# 08_STORE.net
KiCad netlist of a schematic drawn in EAGLE
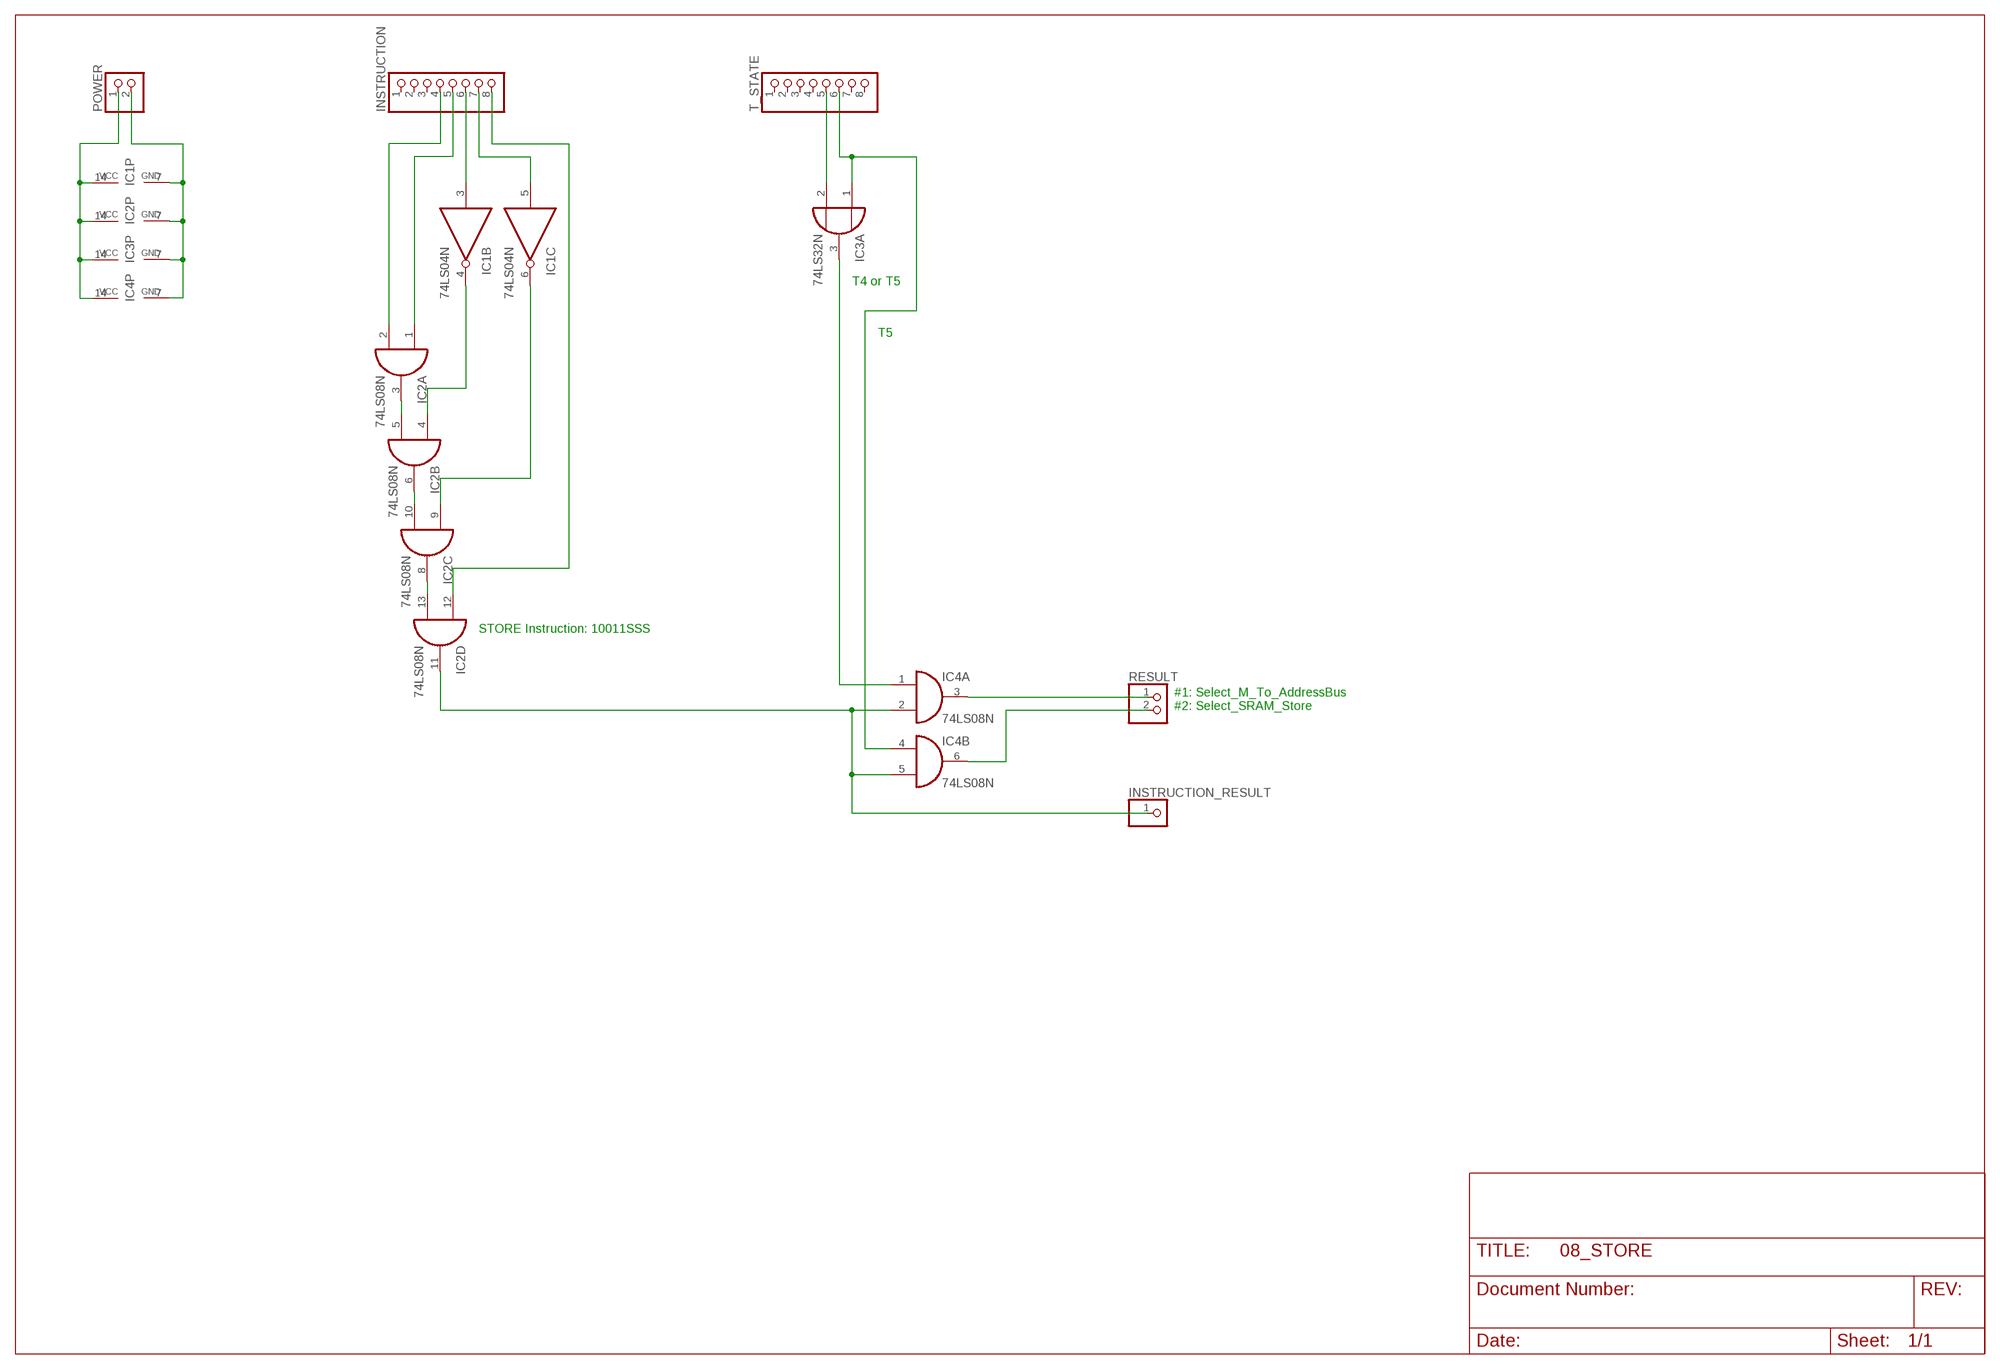
[diagram p0: schematic, sheet 1]

(export (version "E")
  (design (tool "Eeschema 10.0.6"))
  (components
    (comp (ref "IC1")
      (value "74LS04N")
      (footprint "eagle-import:DIL14")
      (libsource (lib "eagle-import") (part "7404NLS"))
    )
    (comp (ref "IC2")
      (value "74LS08N")
      (footprint "eagle-import:DIL14")
      (libsource (lib "eagle-import") (part "7408NLS"))
    )
    (comp (ref "IC3")
      (value "74LS32N")
      (footprint "eagle-import:DIL14")
      (libsource (lib "eagle-import") (part "7432NLS"))
    )
    (comp (ref "IC4")
      (value "74LS08N")
      (footprint "eagle-import:DIL14")
      (libsource (lib "eagle-import") (part "7408NLS"))
    )
    (comp (ref "INSTRUCTION")
      (value "PINHD-1X8")
      (footprint "eagle-import:1X08")
      (libsource (lib "eagle-import") (part "PINHD-1X8"))
    )
    (comp (ref "INSTRUCTION_RESULT")
      (value "PINHD-1X1")
      (footprint "eagle-import:1X01")
      (libsource (lib "eagle-import") (part "PINHD-1X1"))
    )
    (comp (ref "POWER")
      (value "PINHD-1X2")
      (footprint "eagle-import:1X02")
      (libsource (lib "eagle-import") (part "PINHD-1X2"))
    )
    (comp (ref "RESULT")
      (value "PINHD-1X2")
      (footprint "eagle-import:1X02")
      (libsource (lib "eagle-import") (part "PINHD-1X2"))
    )
    (comp (ref "T_STATE")
      (value "PINHD-1X8")
      (footprint "eagle-import:1X08")
      (libsource (lib "eagle-import") (part "PINHD-1X8"))
    )
  )
  (nets
    (net (code "1") (name "Net-(IC1B-I)") (class "Default")
      (node (ref "IC1") (pin "3") (pinfunction "I_3") (pintype "input"))
      (node (ref "INSTRUCTION") (pin "6") (pinfunction "6_6") (pintype "passive"))
    )
    (net (code "2") (name "Net-(IC1B-O)") (class "Default")
      (node (ref "IC1") (pin "4") (pinfunction "O_4") (pintype "output"))
      (node (ref "IC2") (pin "4") (pinfunction "I0_4") (pintype "input"))
    )
    (net (code "3") (name "Net-(IC1C-I)") (class "Default")
      (node (ref "IC1") (pin "5") (pinfunction "I_5") (pintype "input"))
      (node (ref "INSTRUCTION") (pin "7") (pinfunction "7_7") (pintype "passive"))
    )
    (net (code "4") (name "Net-(IC1C-O)") (class "Default")
      (node (ref "IC1") (pin "6") (pinfunction "O_6") (pintype "output"))
      (node (ref "IC2") (pin "9") (pinfunction "I0_9") (pintype "input"))
    )
    (net (code "5") (name "Net-(IC1G-GND)") (class "Default")
      (node (ref "IC1") (pin "7") (pinfunction "GND_7") (pintype "power_in"))
      (node (ref "IC2") (pin "7") (pinfunction "GND_7") (pintype "power_in"))
      (node (ref "IC3") (pin "7") (pinfunction "GND_7") (pintype "power_in"))
      (node (ref "IC4") (pin "7") (pinfunction "GND_7") (pintype "power_in"))
      (node (ref "POWER") (pin "2") (pinfunction "2_2") (pintype "passive"))
    )
    (net (code "6") (name "Net-(IC1G-VCC)") (class "Default")
      (node (ref "IC1") (pin "14") (pinfunction "VCC_14") (pintype "power_in"))
      (node (ref "IC2") (pin "14") (pinfunction "VCC_14") (pintype "power_in"))
      (node (ref "IC3") (pin "14") (pinfunction "VCC_14") (pintype "power_in"))
      (node (ref "IC4") (pin "14") (pinfunction "VCC_14") (pintype "power_in"))
      (node (ref "POWER") (pin "1") (pinfunction "1_1") (pintype "passive"))
    )
    (net (code "7") (name "Net-(IC2A-I0)") (class "Default")
      (node (ref "IC2") (pin "1") (pinfunction "I0_1") (pintype "input"))
      (node (ref "INSTRUCTION") (pin "5") (pinfunction "5_5") (pintype "passive"))
    )
    (net (code "8") (name "Net-(IC2A-I1)") (class "Default")
      (node (ref "IC2") (pin "2") (pinfunction "I1_2") (pintype "input"))
      (node (ref "INSTRUCTION") (pin "4") (pinfunction "4_4") (pintype "passive"))
    )
    (net (code "9") (name "Net-(IC2A-O)") (class "Default")
      (node (ref "IC2") (pin "3") (pinfunction "O_3") (pintype "output"))
      (node (ref "IC2") (pin "5") (pinfunction "I1_5") (pintype "input"))
    )
    (net (code "10") (name "Net-(IC2B-O)") (class "Default")
      (node (ref "IC2") (pin "10") (pinfunction "I1_10") (pintype "input"))
      (node (ref "IC2") (pin "6") (pinfunction "O_6") (pintype "output"))
    )
    (net (code "11") (name "Net-(IC2C-O)") (class "Default")
      (node (ref "IC2") (pin "13") (pinfunction "I1_13") (pintype "input"))
      (node (ref "IC2") (pin "8") (pinfunction "O_8") (pintype "output"))
    )
    (net (code "12") (name "Net-(IC2D-I0)") (class "Default")
      (node (ref "IC2") (pin "12") (pinfunction "I0_12") (pintype "input"))
      (node (ref "INSTRUCTION") (pin "8") (pinfunction "8_8") (pintype "passive"))
    )
    (net (code "13") (name "Net-(IC2D-O)") (class "Default")
      (node (ref "IC2") (pin "11") (pinfunction "O_11") (pintype "output"))
      (node (ref "IC4") (pin "2") (pinfunction "I1_2") (pintype "input"))
      (node (ref "IC4") (pin "5") (pinfunction "I1_5") (pintype "input"))
      (node (ref "INSTRUCTION_RESULT") (pin "1") (pinfunction "1_1") (pintype "passive"))
    )
    (net (code "14") (name "Net-(IC3A-I0)") (class "Default")
      (node (ref "IC3") (pin "1") (pinfunction "I0_1") (pintype "input"))
      (node (ref "IC4") (pin "4") (pinfunction "I0_4") (pintype "input"))
      (node (ref "T_STATE") (pin "6") (pinfunction "6_6") (pintype "passive"))
    )
    (net (code "15") (name "Net-(IC3A-I1)") (class "Default")
      (node (ref "IC3") (pin "2") (pinfunction "I1_2") (pintype "input"))
      (node (ref "T_STATE") (pin "5") (pinfunction "5_5") (pintype "passive"))
    )
    (net (code "16") (name "Net-(IC3A-O)") (class "Default")
      (node (ref "IC3") (pin "3") (pinfunction "O_3") (pintype "output"))
      (node (ref "IC4") (pin "1") (pinfunction "I0_1") (pintype "input"))
    )
    (net (code "17") (name "Net-(IC4A-O)") (class "Default")
      (node (ref "IC4") (pin "3") (pinfunction "O_3") (pintype "output"))
      (node (ref "RESULT") (pin "1") (pinfunction "1_1") (pintype "passive"))
    )
    (net (code "18") (name "Net-(IC4B-O)") (class "Default")
      (node (ref "IC4") (pin "6") (pinfunction "O_6") (pintype "output"))
      (node (ref "RESULT") (pin "2") (pinfunction "2_2") (pintype "passive"))
    )
    (net (code "19") (name "unconnected-(INSTRUCTION-Pad1)") (class "Default")
      (node (ref "INSTRUCTION") (pin "1") (pinfunction "1_1") (pintype "passive"))
    )
    (net (code "20") (name "unconnected-(INSTRUCTION-Pad2)") (class "Default")
      (node (ref "INSTRUCTION") (pin "2") (pinfunction "2_2") (pintype "passive"))
    )
    (net (code "21") (name "unconnected-(INSTRUCTION-Pad3)") (class "Default")
      (node (ref "INSTRUCTION") (pin "3") (pinfunction "3_3") (pintype "passive"))
    )
    (net (code "22") (name "unconnected-(T_STATE-Pad1)") (class "Default")
      (node (ref "T_STATE") (pin "1") (pinfunction "1_1") (pintype "passive"))
    )
    (net (code "23") (name "unconnected-(T_STATE-Pad2)") (class "Default")
      (node (ref "T_STATE") (pin "2") (pinfunction "2_2") (pintype "passive"))
    )
    (net (code "24") (name "unconnected-(T_STATE-Pad3)") (class "Default")
      (node (ref "T_STATE") (pin "3") (pinfunction "3_3") (pintype "passive"))
    )
    (net (code "25") (name "unconnected-(T_STATE-Pad4)") (class "Default")
      (node (ref "T_STATE") (pin "4") (pinfunction "4_4") (pintype "passive"))
    )
    (net (code "26") (name "unconnected-(T_STATE-Pad7)") (class "Default")
      (node (ref "T_STATE") (pin "7") (pinfunction "7_7") (pintype "passive"))
    )
    (net (code "27") (name "unconnected-(T_STATE-Pad8)") (class "Default")
      (node (ref "T_STATE") (pin "8") (pinfunction "8_8") (pintype "passive"))
    )
  )
)
